# RFM2Pi_rev3.net
KiCad netlist of a schematic drawn in EAGLE
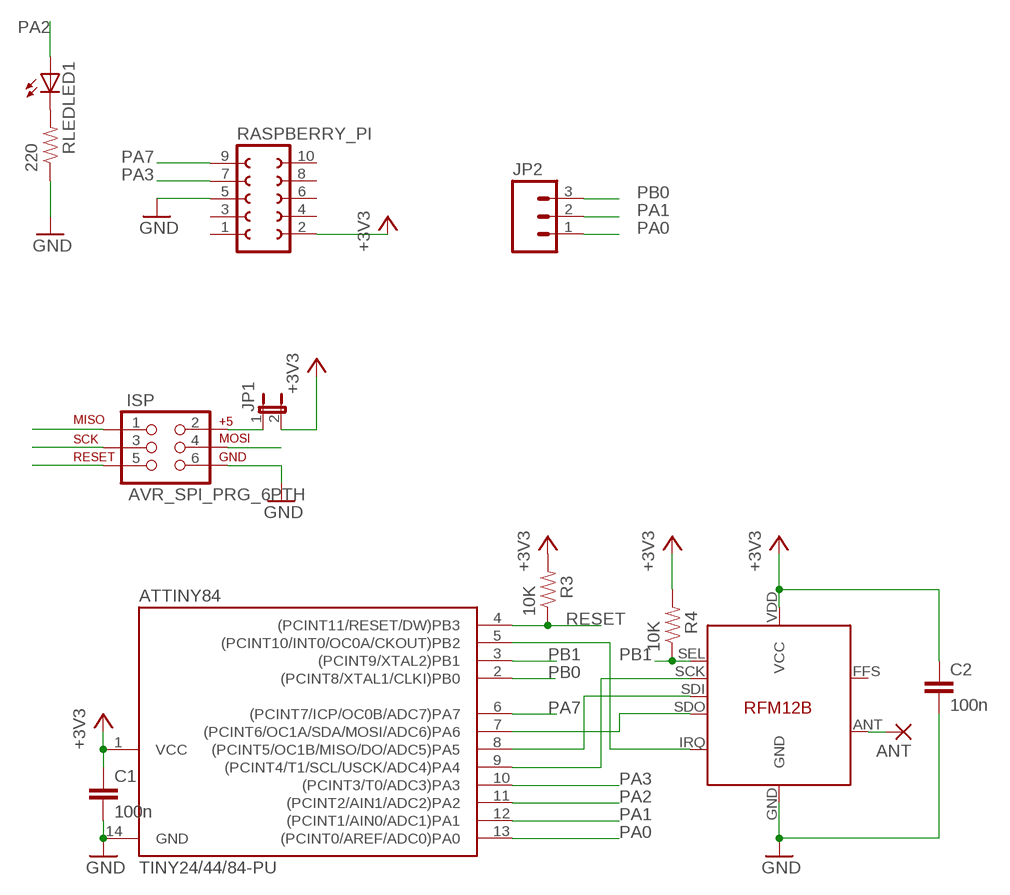
[diagram p0: schematic, sheet 1]

(export (version "E")
  (design (tool "Eeschema 10.0.6"))
  (components
    (comp (ref "ANT")
      (value "1,6/0,8")
      (footprint "eagle-import:1,6_0,8")
      (libsource (lib "eagle-import") (part "1,6/0,8"))
    )
    (comp (ref "ATTINY84")
      (value "TINY24/44/84-PU")
      (footprint "eagle-import:DIL14")
      (libsource (lib "eagle-import") (part "TINY24/44/84-PU"))
    )
    (comp (ref "C1")
      (value "100n")
      (footprint "eagle-import:C025-024X044")
      (libsource (lib "eagle-import") (part "C-EU025-024X044"))
    )
    (comp (ref "C2")
      (value "100n")
      (footprint "eagle-import:C025-024X044")
      (libsource (lib "eagle-import") (part "C-EU025-024X044"))
    )
    (comp (ref "ISP")
      (value "AVR_SPI_PRG_6PTH")
      (footprint "eagle-import:2X3")
      (libsource (lib "eagle-import") (part "AVR_SPI_PRG_6PTH"))
    )
    (comp (ref "JP1")
      (value "JUMPER-2PTH")
      (footprint "eagle-import:1X02")
      (libsource (lib "eagle-import") (part "JUMPER-2PTH"))
    )
    (comp (ref "JP2")
      (value "M03LOCK")
      (footprint "eagle-import:1X03_LOCK")
      (libsource (lib "eagle-import") (part "M03LOCK"))
    )
    (comp (ref "LED1")
      (value "LED5MM")
      (footprint "eagle-import:LED5MM")
      (libsource (lib "eagle-import") (part "LED5MM"))
    )
    (comp (ref "R3")
      (value "10K")
      (footprint "eagle-import:AXIAL-0.3")
      (libsource (lib "eagle-import") (part "RESISTORAXIAL-0.3"))
    )
    (comp (ref "R4")
      (value "10K")
      (footprint "eagle-import:AXIAL-0.3")
      (libsource (lib "eagle-import") (part "RESISTORAXIAL-0.3"))
    )
    (comp (ref "RASPBERRY_PI")
      (value "FE05-2")
      (footprint "eagle-import:FE05-2")
      (libsource (lib "eagle-import") (part "FE05-2"))
    )
    (comp (ref "RFM12B")
      (value "RFM12B")
      (footprint "eagle-import:RFM12B")
      (libsource (lib "eagle-import") (part "RFM12B"))
    )
    (comp (ref "RLED")
      (value "220")
      (footprint "eagle-import:AXIAL-0.3")
      (libsource (lib "eagle-import") (part "RESISTORAXIAL-0.3"))
    )
  )
  (nets
    (net (code "1") (name "+3V3") (class "Default")
      (node (ref "ATTINY84") (pin "1") (pinfunction "VCC_1") (pintype "power_in"))
      (node (ref "C1") (pin "1") (pinfunction "1_1") (pintype "passive"))
      (node (ref "C2") (pin "1") (pinfunction "1_1") (pintype "passive"))
      (node (ref "JP1") (pin "2") (pinfunction "2_2") (pintype "passive"))
      (node (ref "R3") (pin "P$2") (pinfunction "2_P$2") (pintype "passive"))
      (node (ref "R4") (pin "P$2") (pinfunction "2_P$2") (pintype "passive"))
      (node (ref "RASPBERRY_PI") (pin "2") (pinfunction "2_2") (pintype "passive"))
      (node (ref "RFM12B") (pin "VDD") (pinfunction "VCC_VDD") (pintype "power_in"))
    )
    (net (code "2") (name "/MISO") (class "Default")
      (node (ref "ATTINY84") (pin "8") (pinfunction "(PCINT5/OC1B/MISO/DO/ADC5)PA5_8") (pintype "bidirectional"))
      (node (ref "ISP") (pin "1") (pinfunction "1_1") (pintype "passive"))
      (node (ref "RFM12B") (pin "SDI") (pinfunction "SDI_SDI") (pintype "input"))
    )
    (net (code "3") (name "/MOSI") (class "Default")
      (node (ref "ATTINY84") (pin "7") (pinfunction "(PCINT6/OC1A/SDA/MOSI/ADC6)PA6_7") (pintype "bidirectional"))
      (node (ref "ISP") (pin "4") (pinfunction "4_4") (pintype "passive"))
      (node (ref "RFM12B") (pin "SDO") (pinfunction "SDO_SDO") (pintype "output"))
    )
    (net (code "4") (name "/PA0") (class "Default")
      (node (ref "ATTINY84") (pin "13") (pinfunction "(PCINT0/AREF/ADC0)PA0_13") (pintype "bidirectional"))
      (node (ref "JP2") (pin "1") (pinfunction "1_1") (pintype "passive"))
    )
    (net (code "5") (name "/PA1") (class "Default")
      (node (ref "ATTINY84") (pin "12") (pinfunction "(PCINT1/AIN0/ADC1)PA1_12") (pintype "bidirectional"))
      (node (ref "JP2") (pin "2") (pinfunction "2_2") (pintype "passive"))
    )
    (net (code "6") (name "/PA2") (class "Default")
      (node (ref "ATTINY84") (pin "11") (pinfunction "(PCINT2/AIN1/ADC2)PA2_11") (pintype "bidirectional"))
      (node (ref "LED1") (pin "A") (pinfunction "A_A") (pintype "passive"))
    )
    (net (code "7") (name "/PA3") (class "Default")
      (node (ref "ATTINY84") (pin "10") (pinfunction "(PCINT3/T0/ADC3)PA3_10") (pintype "bidirectional"))
      (node (ref "RASPBERRY_PI") (pin "7") (pinfunction "7_7") (pintype "passive"))
    )
    (net (code "8") (name "/PA7") (class "Default")
      (node (ref "ATTINY84") (pin "6") (pinfunction "(PCINT7/ICP/OC0B/ADC7)PA7_6") (pintype "bidirectional"))
      (node (ref "RASPBERRY_PI") (pin "9") (pinfunction "9_9") (pintype "passive"))
    )
    (net (code "9") (name "/PB0") (class "Default")
      (node (ref "ATTINY84") (pin "2") (pinfunction "(PCINT8/XTAL1/CLKI)PB0_2") (pintype "bidirectional"))
      (node (ref "JP2") (pin "3") (pinfunction "3_3") (pintype "passive"))
    )
    (net (code "10") (name "/PB1") (class "Default")
      (node (ref "ATTINY84") (pin "3") (pinfunction "(PCINT9/XTAL2)PB1_3") (pintype "bidirectional"))
      (node (ref "R4") (pin "P$1") (pinfunction "1_P$1") (pintype "passive"))
      (node (ref "RFM12B") (pin "SEL") (pinfunction "SEL_SEL") (pintype "input"))
    )
    (net (code "11") (name "/RESET") (class "Default")
      (node (ref "ATTINY84") (pin "4") (pinfunction "(PCINT11/RESET/DW)PB3_4") (pintype "bidirectional"))
      (node (ref "ISP") (pin "5") (pinfunction "5_5") (pintype "passive"))
      (node (ref "R3") (pin "P$1") (pinfunction "1_P$1") (pintype "passive"))
    )
    (net (code "12") (name "/SCK") (class "Default")
      (node (ref "ATTINY84") (pin "9") (pinfunction "(PCINT4/T1/SCL/USCK/ADC4)PA4_9") (pintype "bidirectional"))
      (node (ref "ISP") (pin "3") (pinfunction "3_3") (pintype "passive"))
      (node (ref "RFM12B") (pin "SCK") (pinfunction "SCK_SCK") (pintype "input"))
    )
    (net (code "13") (name "GND") (class "Default")
      (node (ref "ATTINY84") (pin "14") (pinfunction "GND_14") (pintype "power_in"))
      (node (ref "C1") (pin "2") (pinfunction "2_2") (pintype "passive"))
      (node (ref "C2") (pin "2") (pinfunction "2_2") (pintype "passive"))
      (node (ref "ISP") (pin "6") (pinfunction "6_6") (pintype "passive"))
      (node (ref "RASPBERRY_PI") (pin "5") (pinfunction "5_5") (pintype "passive"))
      (node (ref "RFM12B") (pin "GND") (pinfunction "GND_GND") (pintype "power_in"))
      (node (ref "RLED") (pin "P$1") (pinfunction "1_P$1") (pintype "passive"))
    )
    (net (code "14") (name "Net-(ANT-P)") (class "Default")
      (node (ref "ANT") (pin "1") (pinfunction "P_1") (pintype "passive"))
      (node (ref "RFM12B") (pin "ANT") (pinfunction "ANT_ANT") (pintype "passive"))
    )
    (net (code "15") (name "Net-(ATTINY84-(PCINT10{slash}INT0{slash}OC0A{slash}CKOUT)PB2)") (class "Default")
      (node (ref "ATTINY84") (pin "5") (pinfunction "(PCINT10/INT0/OC0A/CKOUT)PB2_5") (pintype "bidirectional"))
      (node (ref "RFM12B") (pin "IRQ") (pinfunction "IRQ_IRQ") (pintype "open_collector"))
    )
    (net (code "16") (name "Net-(ISP-Pad2)") (class "Default")
      (node (ref "ISP") (pin "2") (pinfunction "2_2") (pintype "passive"))
      (node (ref "JP1") (pin "1") (pinfunction "1_1") (pintype "passive"))
    )
    (net (code "17") (name "Net-(LED1-C)") (class "Default")
      (node (ref "LED1") (pin "K") (pinfunction "C_K") (pintype "passive"))
      (node (ref "RLED") (pin "P$2") (pinfunction "2_P$2") (pintype "passive"))
    )
    (net (code "18") (name "unconnected-(RASPBERRY_PI-Pad1)") (class "Default")
      (node (ref "RASPBERRY_PI") (pin "1") (pinfunction "1_1") (pintype "passive"))
    )
    (net (code "19") (name "unconnected-(RASPBERRY_PI-Pad3)") (class "Default")
      (node (ref "RASPBERRY_PI") (pin "3") (pinfunction "3_3") (pintype "passive"))
    )
    (net (code "20") (name "unconnected-(RASPBERRY_PI-Pad4)") (class "Default")
      (node (ref "RASPBERRY_PI") (pin "4") (pinfunction "4_4") (pintype "passive"))
    )
    (net (code "21") (name "unconnected-(RASPBERRY_PI-Pad6)") (class "Default")
      (node (ref "RASPBERRY_PI") (pin "6") (pinfunction "6_6") (pintype "passive"))
    )
    (net (code "22") (name "unconnected-(RASPBERRY_PI-Pad8)") (class "Default")
      (node (ref "RASPBERRY_PI") (pin "8") (pinfunction "8_8") (pintype "passive"))
    )
    (net (code "23") (name "unconnected-(RASPBERRY_PI-Pad10)") (class "Default")
      (node (ref "RASPBERRY_PI") (pin "10") (pinfunction "10_10") (pintype "passive"))
    )
    (net (code "24") (name "unconnected-(RFM12B-PadFFS)") (class "Default")
      (node (ref "RFM12B") (pin "FFS") (pinfunction "FFS_FFS") (pintype "bidirectional"))
    )
  )
)
